# Gastroscopy-Tool-Sensor_LED.net
KiCad netlist of a schematic drawn in Altium Designer
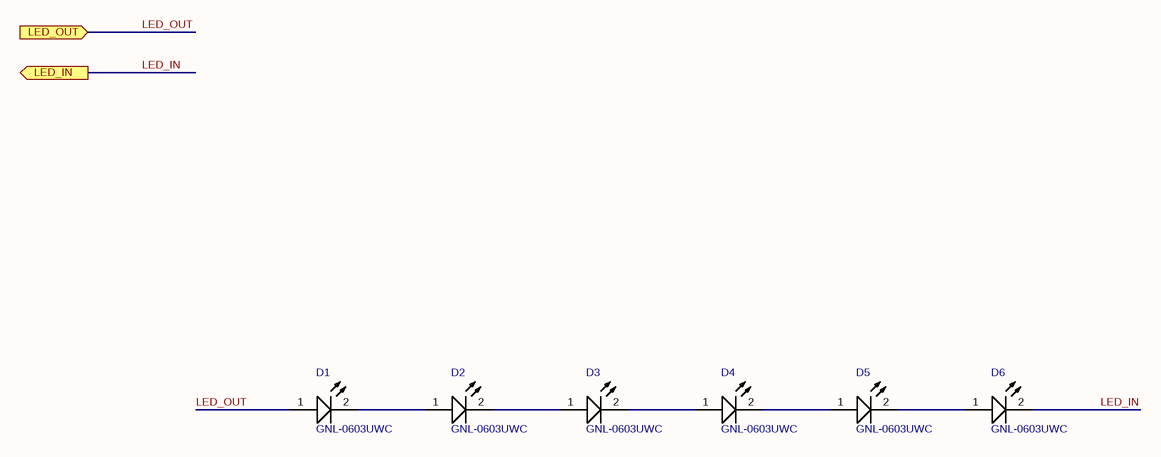
[diagram p0: Gastroscopy-Tool-Sensor_LED.SchDoc]

(export (version "E")
  (design (tool "Eeschema 10.0.6"))
  (components
    (comp (ref "D1")
      (value "GNL-0603UWC")
      (footprint "L_0603_WHITE")
      (description "LED WHITE CLEAR SMD")
      (libsource (lib "Gastroscopy-Tool") (part "GNL-0603UWC"))
    )
    (comp (ref "D2")
      (value "GNL-0603UWC")
      (footprint "L_0603_WHITE")
      (description "LED WHITE CLEAR SMD")
      (libsource (lib "Gastroscopy-Tool") (part "GNL-0603UWC"))
    )
    (comp (ref "D3")
      (value "GNL-0603UWC")
      (footprint "L_0603_WHITE")
      (description "LED WHITE CLEAR SMD")
      (libsource (lib "Gastroscopy-Tool") (part "GNL-0603UWC"))
    )
    (comp (ref "D4")
      (value "GNL-0603UWC")
      (footprint "L_0603_WHITE")
      (description "LED WHITE CLEAR SMD")
      (libsource (lib "Gastroscopy-Tool") (part "GNL-0603UWC"))
    )
    (comp (ref "D5")
      (value "GNL-0603UWC")
      (footprint "L_0603_WHITE")
      (description "LED WHITE CLEAR SMD")
      (libsource (lib "Gastroscopy-Tool") (part "GNL-0603UWC"))
    )
    (comp (ref "D6")
      (value "GNL-0603UWC")
      (footprint "L_0603_WHITE")
      (description "LED WHITE CLEAR SMD")
      (libsource (lib "Gastroscopy-Tool") (part "GNL-0603UWC"))
    )
  )
  (nets
    (net (code "1") (name "/LED_IN") (class "Default")
      (node (ref "D6") (pin "2") (pinfunction "K_2") (pintype "passive"))
    )
    (net (code "2") (name "/LED_OUT") (class "Default")
      (node (ref "D1") (pin "1") (pinfunction "A_1") (pintype "passive"))
    )
    (net (code "3") (name "Net-(D1-K)") (class "Default")
      (node (ref "D1") (pin "2") (pinfunction "K_2") (pintype "passive"))
      (node (ref "D2") (pin "1") (pinfunction "A_1") (pintype "passive"))
    )
    (net (code "4") (name "Net-(D2-K)") (class "Default")
      (node (ref "D2") (pin "2") (pinfunction "K_2") (pintype "passive"))
      (node (ref "D3") (pin "1") (pinfunction "A_1") (pintype "passive"))
    )
    (net (code "5") (name "Net-(D3-K)") (class "Default")
      (node (ref "D3") (pin "2") (pinfunction "K_2") (pintype "passive"))
      (node (ref "D4") (pin "1") (pinfunction "A_1") (pintype "passive"))
    )
    (net (code "6") (name "Net-(D4-K)") (class "Default")
      (node (ref "D4") (pin "2") (pinfunction "K_2") (pintype "passive"))
      (node (ref "D5") (pin "1") (pinfunction "A_1") (pintype "passive"))
    )
    (net (code "7") (name "Net-(D5-K)") (class "Default")
      (node (ref "D5") (pin "2") (pinfunction "K_2") (pintype "passive"))
      (node (ref "D6") (pin "1") (pinfunction "A_1") (pintype "passive"))
    )
  )
)
